# Sch.net
KiCad netlist of a schematic drawn in Altium Designer
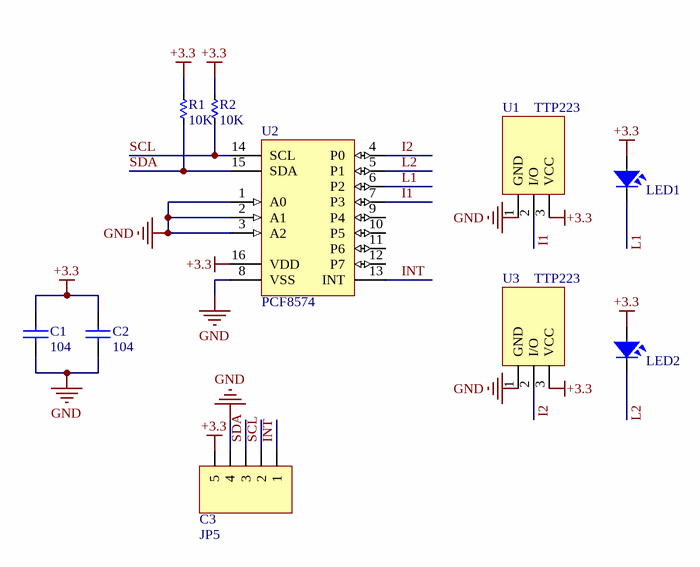
[diagram p0: Sch.SchDoc]

(export (version "E")
  (design (tool "Eeschema 10.0.6"))
  (components
    (comp (ref "C1")
      (value "104")
      (footprint "tu 0805")
      (description "Dán")
      (libsource (lib "Altium_Lib_by_KhueNguyenCreator") (part "Tu 0805 104 50V 10%"))
    )
    (comp (ref "C2")
      (value "104")
      (footprint "tu 0805")
      (description "Dán")
      (libsource (lib "Altium_Lib_by_KhueNguyenCreator") (part "Tu 0805 104 50V 10%"))
    )
    (comp (ref "C3")
      (value "JP5")
      (footprint "JP5-SMD-2.54")
      (description "WR-PHD 2.54 mm Angled Socket Header")
      (fields
        (field (name "MANUFACTURER") "Würth Elektronik eiSos GmbH")
        (field (name "PARTNO") "613005143121")
        (field (name "CREATED BY") "Karrer Zheng")
      )
      (libsource (lib "iuh-thuc-hanh") (part "JP5"))
    )
    (comp (ref "LED1")
      (value "LED")
      (footprint "LED-5-RED")
      (description "LED Single colour Green and Red")
      (libsource (lib "LIBRARY1") (part "LED"))
    )
    (comp (ref "LED2")
      (value "LED")
      (footprint "LED-5-RED")
      (description "LED Single colour Green and Red")
      (libsource (lib "LIBRARY1") (part "LED"))
    )
    (comp (ref "R1")
      (value "10K")
      (footprint "RES-1/4W")
      (description "Res")
      (fields
        (field (name "MANUFACTURER") "Generic Components")
        (field (name "PUBLISHER") "Altium Hobart Technology Centre")
      )
      (libsource (lib "LIBRARY1") (part "Res"))
    )
    (comp (ref "R2")
      (value "10K")
      (footprint "RES-1/4W")
      (description "Res")
      (fields
        (field (name "MANUFACTURER") "Generic Components")
        (field (name "PUBLISHER") "Altium Hobart Technology Centre")
      )
      (libsource (lib "LIBRARY1") (part "Res"))
    )
    (comp (ref "U1")
      (value "TTP223")
      (footprint "Module TTP223")
      (libsource (lib "iuh-thuc-hanh") (part "Module TTP223"))
    )
    (comp (ref "U2") (value "PCF8574") (footprint "DIP16") (libsource (lib "iuh-thuc-hanh") (part "PCF8574")))
    (comp (ref "U3")
      (value "TTP223")
      (footprint "Module TTP223")
      (libsource (lib "iuh-thuc-hanh") (part "Module TTP223"))
    )
  )
  (nets
    (net (code "1") (name "+3.3") (class "Default")
      (node (ref "C1") (pin "1") (pinfunction "1_1") (pintype "passive"))
      (node (ref "C2") (pin "1") (pinfunction "1_1") (pintype "passive"))
      (node (ref "C3") (pin "5") (pinfunction "5_5") (pintype "passive"))
      (node (ref "LED1") (pin "1") (pinfunction "1_1") (pintype "passive"))
      (node (ref "LED2") (pin "1") (pinfunction "1_1") (pintype "passive"))
      (node (ref "R1") (pin "1") (pinfunction "1_1") (pintype "passive"))
      (node (ref "R2") (pin "1") (pinfunction "1_1") (pintype "passive"))
      (node (ref "U1") (pin "3") (pinfunction "VCC_3") (pintype "passive"))
      (node (ref "U2") (pin "16") (pinfunction "VDD_16") (pintype "passive"))
      (node (ref "U3") (pin "3") (pinfunction "VCC_3") (pintype "passive"))
    )
    (net (code "2") (name "/I1") (class "Default")
      (node (ref "U1") (pin "2") (pinfunction "I/O_2") (pintype "passive"))
      (node (ref "U2") (pin "7") (pinfunction "P3_7") (pintype "bidirectional"))
    )
    (net (code "3") (name "/I2") (class "Default")
      (node (ref "U2") (pin "4") (pinfunction "P0_4") (pintype "bidirectional"))
      (node (ref "U3") (pin "2") (pinfunction "I/O_2") (pintype "passive"))
    )
    (net (code "4") (name "/INT") (class "Default")
      (node (ref "C3") (pin "1") (pinfunction "1_1") (pintype "passive"))
      (node (ref "U2") (pin "13") (pinfunction "INT_13") (pintype "passive"))
    )
    (net (code "5") (name "/L1") (class "Default")
      (node (ref "LED1") (pin "2") (pinfunction "2_2") (pintype "passive"))
      (node (ref "U2") (pin "6") (pinfunction "P2_6") (pintype "bidirectional"))
    )
    (net (code "6") (name "/L2") (class "Default")
      (node (ref "LED2") (pin "2") (pinfunction "2_2") (pintype "passive"))
      (node (ref "U2") (pin "5") (pinfunction "P1_5") (pintype "bidirectional"))
    )
    (net (code "7") (name "/SCL") (class "Default")
      (node (ref "C3") (pin "2") (pinfunction "2_2") (pintype "passive"))
      (node (ref "R2") (pin "2") (pinfunction "2_2") (pintype "passive"))
      (node (ref "U2") (pin "14") (pinfunction "SCL_14") (pintype "passive"))
    )
    (net (code "8") (name "/SDA") (class "Default")
      (node (ref "C3") (pin "3") (pinfunction "3_3") (pintype "passive"))
      (node (ref "R1") (pin "2") (pinfunction "2_2") (pintype "passive"))
      (node (ref "U2") (pin "15") (pinfunction "SDA_15") (pintype "passive"))
    )
    (net (code "9") (name "GND") (class "Default")
      (node (ref "C1") (pin "2") (pinfunction "2_2") (pintype "passive"))
      (node (ref "C2") (pin "2") (pinfunction "2_2") (pintype "passive"))
      (node (ref "C3") (pin "4") (pinfunction "4_4") (pintype "passive"))
      (node (ref "U1") (pin "1") (pinfunction "GND_1") (pintype "passive"))
      (node (ref "U2") (pin "1") (pinfunction "A0_1") (pintype "input"))
      (node (ref "U2") (pin "2") (pinfunction "A1_2") (pintype "input"))
      (node (ref "U2") (pin "3") (pinfunction "A2_3") (pintype "input"))
      (node (ref "U2") (pin "8") (pinfunction "VSS_8") (pintype "passive"))
      (node (ref "U3") (pin "1") (pinfunction "GND_1") (pintype "passive"))
    )
    (net (code "10") (name "unconnected-(U2-P4-Pad9)") (class "Default")
      (node (ref "U2") (pin "9") (pinfunction "P4_9") (pintype "bidirectional"))
    )
    (net (code "11") (name "unconnected-(U2-P5-Pad10)") (class "Default")
      (node (ref "U2") (pin "10") (pinfunction "P5_10") (pintype "bidirectional"))
    )
    (net (code "12") (name "unconnected-(U2-P6-Pad11)") (class "Default")
      (node (ref "U2") (pin "11") (pinfunction "P6_11") (pintype "bidirectional"))
    )
    (net (code "13") (name "unconnected-(U2-P7-Pad12)") (class "Default")
      (node (ref "U2") (pin "12") (pinfunction "P7_12") (pintype "bidirectional"))
    )
  )
)
